# digital.net
KiCad netlist of a schematic drawn in EAGLE
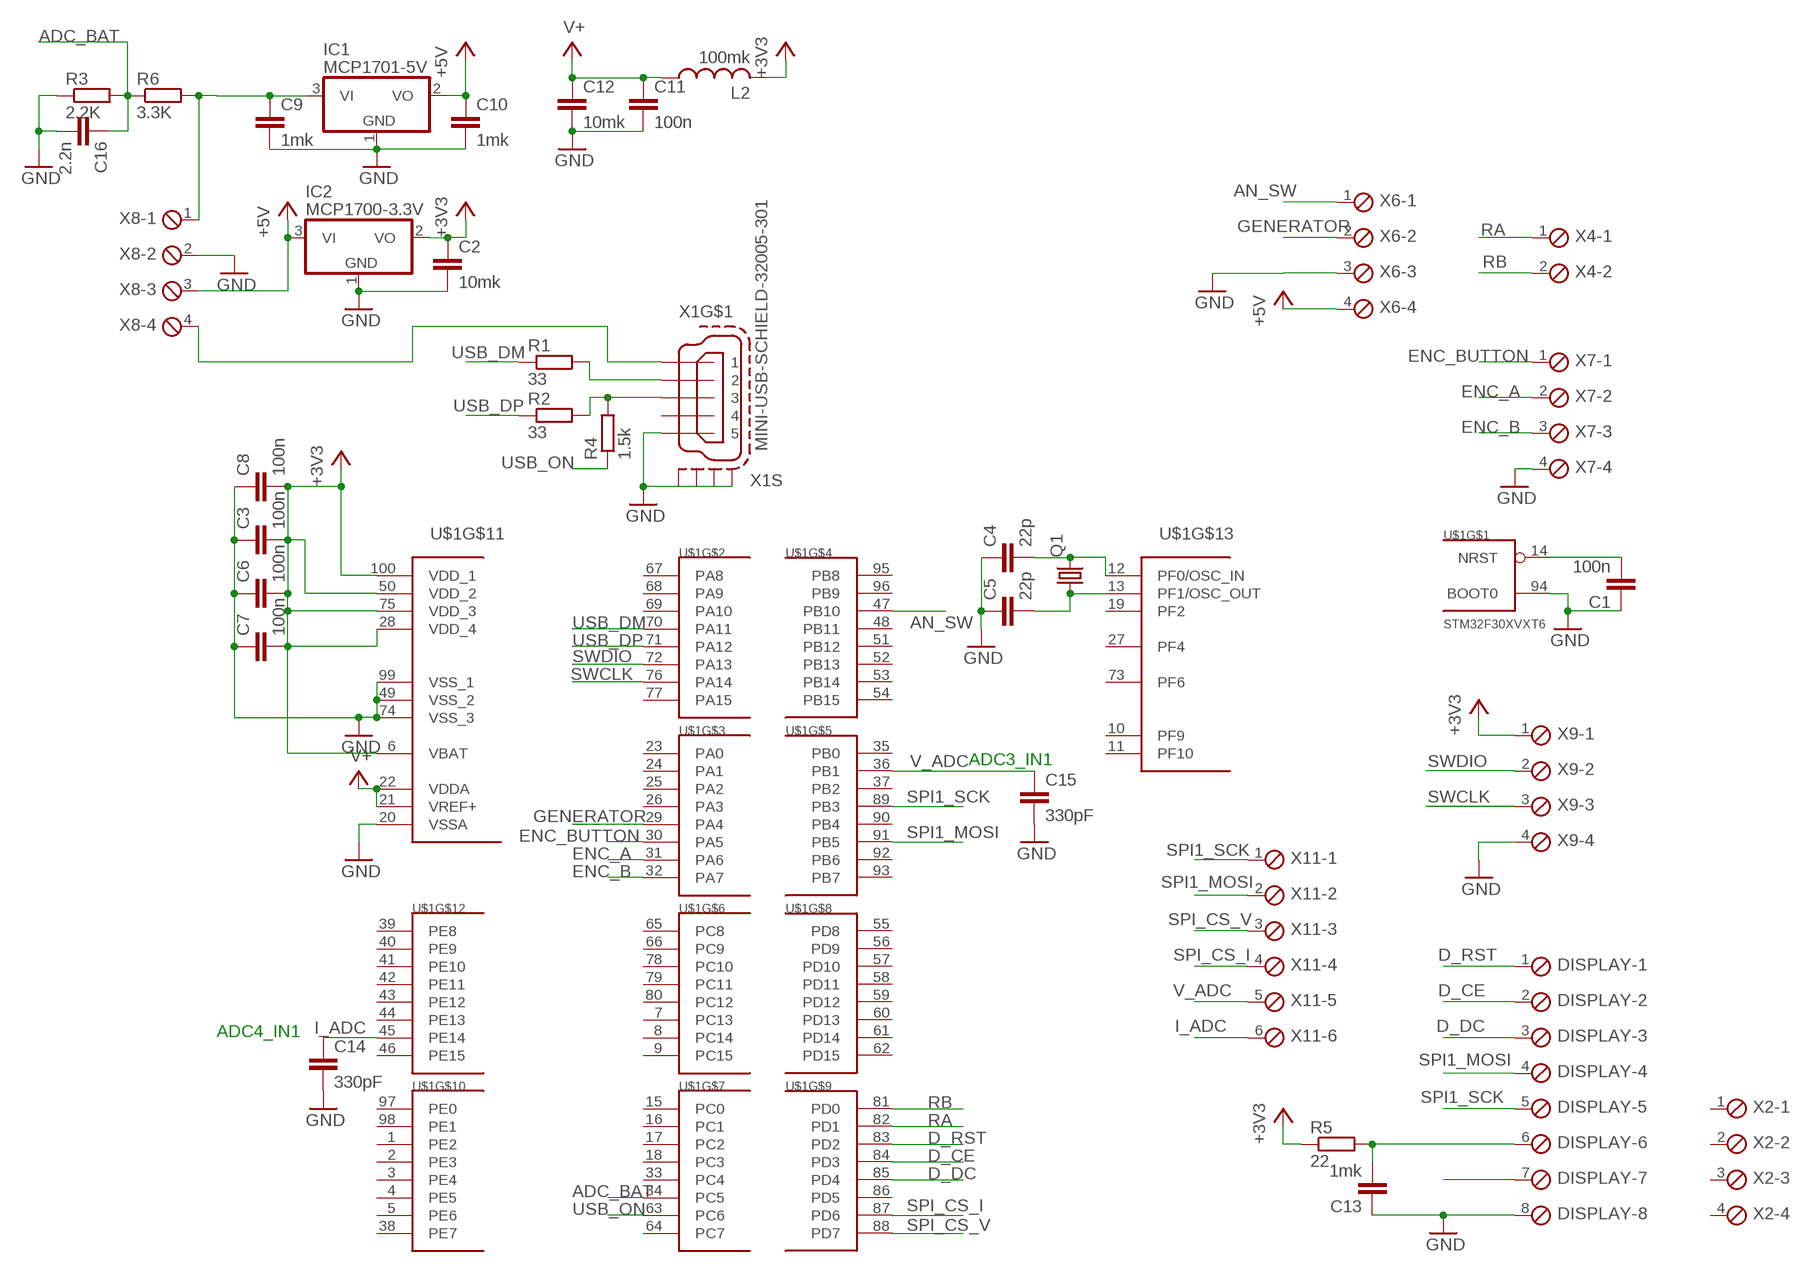
[diagram p0: schematic, sheet 1]

(export (version "E")
  (design (tool "Eeschema 10.0.6"))
  (components
    (comp (ref "C1")
      (value "100n")
      (footprint "eagle-import:C0603")
      (libsource (lib "eagle-import") (part "C-EUC0603"))
    )
    (comp (ref "C2")
      (value "10mk")
      (footprint "eagle-import:C0805")
      (libsource (lib "eagle-import") (part "C-EUC0805"))
    )
    (comp (ref "C3")
      (value "100n")
      (footprint "eagle-import:C0603")
      (libsource (lib "eagle-import") (part "C-EUC0603"))
    )
    (comp (ref "C4")
      (value "22p")
      (footprint "eagle-import:C0805")
      (libsource (lib "eagle-import") (part "C-EUC0805"))
    )
    (comp (ref "C5")
      (value "22p")
      (footprint "eagle-import:C0805")
      (libsource (lib "eagle-import") (part "C-EUC0805"))
    )
    (comp (ref "C6")
      (value "100n")
      (footprint "eagle-import:C0603")
      (libsource (lib "eagle-import") (part "C-EUC0603"))
    )
    (comp (ref "C7")
      (value "100n")
      (footprint "eagle-import:C0603")
      (libsource (lib "eagle-import") (part "C-EUC0603"))
    )
    (comp (ref "C8")
      (value "100n")
      (footprint "eagle-import:C0603")
      (libsource (lib "eagle-import") (part "C-EUC0603"))
    )
    (comp (ref "C9")
      (value "1mk")
      (footprint "eagle-import:C0603")
      (libsource (lib "eagle-import") (part "C-EUC0603"))
    )
    (comp (ref "C10")
      (value "1mk")
      (footprint "eagle-import:C0603")
      (libsource (lib "eagle-import") (part "C-EUC0603"))
    )
    (comp (ref "C11")
      (value "100n")
      (footprint "eagle-import:C0603")
      (libsource (lib "eagle-import") (part "C-EUC0603"))
    )
    (comp (ref "C12")
      (value "10mk")
      (footprint "eagle-import:C0805")
      (libsource (lib "eagle-import") (part "C-EUC0805"))
    )
    (comp (ref "C13")
      (value "1mk")
      (footprint "eagle-import:C0603")
      (libsource (lib "eagle-import") (part "C-EUC0603"))
    )
    (comp (ref "C14")
      (value "330pF")
      (footprint "eagle-import:C0805")
      (libsource (lib "eagle-import") (part "C-EUC0805"))
    )
    (comp (ref "C15")
      (value "330pF")
      (footprint "eagle-import:C0805")
      (libsource (lib "eagle-import") (part "C-EUC0805"))
    )
    (comp (ref "C16")
      (value "2.2n")
      (footprint "eagle-import:C0805")
      (libsource (lib "eagle-import") (part "C-EUC0805"))
    )
    (comp (ref "DISPLAY")
      (value "MPT8")
      (footprint "eagle-import:8POL254")
      (libsource (lib "eagle-import") (part "MPT8"))
    )
    (comp (ref "IC1")
      (value "MCP1701-5V")
      (footprint "eagle-import:SOT23")
      (libsource (lib "eagle-import") (part "MCP1703CB"))
    )
    (comp (ref "IC2")
      (value "MCP1700-3.3V")
      (footprint "eagle-import:SOT23")
      (libsource (lib "eagle-import") (part "MCP1703CB"))
    )
    (comp (ref "L2")
      (value "100mk")
      (footprint "eagle-import:0204_7")
      (libsource (lib "eagle-import") (part "L-US0204/7"))
    )
    (comp (ref "Q1")
      (value "CRYSTALHC49UP")
      (footprint "eagle-import:HC49UP")
      (libsource (lib "eagle-import") (part "CRYSTALHC49UP"))
    )
    (comp (ref "R1")
      (value "33")
      (footprint "eagle-import:R0603")
      (libsource (lib "eagle-import") (part "R-EU_R0603"))
    )
    (comp (ref "R2")
      (value "33")
      (footprint "eagle-import:R0603")
      (libsource (lib "eagle-import") (part "R-EU_R0603"))
    )
    (comp (ref "R3")
      (value "2.2K")
      (footprint "eagle-import:R0603")
      (libsource (lib "eagle-import") (part "R-EU_R0603"))
    )
    (comp (ref "R4")
      (value "1.5k")
      (footprint "eagle-import:R0603")
      (libsource (lib "eagle-import") (part "R-EU_R0603"))
    )
    (comp (ref "R5")
      (value "22")
      (footprint "eagle-import:R0603")
      (libsource (lib "eagle-import") (part "R-EU_R0603"))
    )
    (comp (ref "R6")
      (value "3.3K")
      (footprint "eagle-import:R0603")
      (libsource (lib "eagle-import") (part "R-EU_R0603"))
    )
    (comp (ref "U$1")
      (value "STM32F30XVXT6")
      (footprint "eagle-import:TQFP100")
      (libsource (lib "eagle-import") (part "STM32F30XVXT6"))
    )
    (comp (ref "X1")
      (value "MINI-USB-SCHIELD-32005-301")
      (footprint "eagle-import:32005-301")
      (libsource (lib "eagle-import") (part "MINI-USB-SCHIELD-32005-301"))
    )
    (comp (ref "X2")
      (value "MPT4")
      (footprint "eagle-import:4POL254")
      (libsource (lib "eagle-import") (part "MPT4"))
    )
    (comp (ref "X4")
      (value "MPT2")
      (footprint "eagle-import:2POL254")
      (libsource (lib "eagle-import") (part "MPT2"))
    )
    (comp (ref "X6")
      (value "MPT4")
      (footprint "eagle-import:4POL254")
      (libsource (lib "eagle-import") (part "MPT4"))
    )
    (comp (ref "X7")
      (value "MPT4")
      (footprint "eagle-import:4POL254")
      (libsource (lib "eagle-import") (part "MPT4"))
    )
    (comp (ref "X8")
      (value "MPT4")
      (footprint "eagle-import:4POL254")
      (libsource (lib "eagle-import") (part "MPT4"))
    )
    (comp (ref "X9")
      (value "MPT4")
      (footprint "eagle-import:4POL254")
      (libsource (lib "eagle-import") (part "MPT4"))
    )
    (comp (ref "X11")
      (value "MPT6")
      (footprint "eagle-import:6POL254")
      (libsource (lib "eagle-import") (part "MPT6"))
    )
  )
  (nets
    (net (code "1") (name "+3V3") (class "Default")
      (node (ref "C2") (pin "1") (pinfunction "1_1") (pintype "passive"))
      (node (ref "C3") (pin "2") (pinfunction "2_2") (pintype "passive"))
      (node (ref "C6") (pin "2") (pinfunction "2_2") (pintype "passive"))
      (node (ref "C7") (pin "2") (pinfunction "2_2") (pintype "passive"))
      (node (ref "C8") (pin "2") (pinfunction "2_2") (pintype "passive"))
      (node (ref "IC2") (pin "2") (pinfunction "VO_2") (pintype "passive"))
      (node (ref "L2") (pin "2") (pinfunction "2_2") (pintype "passive"))
      (node (ref "R5") (pin "1") (pinfunction "1_1") (pintype "passive"))
      (node (ref "U$1") (pin "100") (pinfunction "VDD_1_100") (pintype "bidirectional"))
      (node (ref "U$1") (pin "28") (pinfunction "VDD_4_28") (pintype "bidirectional"))
      (node (ref "U$1") (pin "50") (pinfunction "VDD_2_50") (pintype "bidirectional"))
      (node (ref "U$1") (pin "6") (pinfunction "VBAT_6") (pintype "bidirectional"))
      (node (ref "U$1") (pin "75") (pinfunction "VDD_3_75") (pintype "bidirectional"))
      (node (ref "X9") (pin "1") (pinfunction "1_1") (pintype "passive"))
    )
    (net (code "2") (name "+5V") (class "Default")
      (node (ref "C10") (pin "1") (pinfunction "1_1") (pintype "passive"))
      (node (ref "IC1") (pin "2") (pinfunction "VO_2") (pintype "passive"))
      (node (ref "IC2") (pin "3") (pinfunction "VI_3") (pintype "input"))
      (node (ref "X6") (pin "4") (pinfunction "1_4") (pintype "passive"))
      (node (ref "X8") (pin "3") (pinfunction "1_3") (pintype "passive"))
    )
    (net (code "3") (name "/ADC_BAT") (class "Default")
      (node (ref "C16") (pin "1") (pinfunction "1_1") (pintype "passive"))
      (node (ref "R3") (pin "2") (pinfunction "2_2") (pintype "passive"))
      (node (ref "R6") (pin "1") (pinfunction "1_1") (pintype "passive"))
      (node (ref "U$1") (pin "34") (pinfunction "PC5_34") (pintype "bidirectional"))
    )
    (net (code "4") (name "/AN_SW") (class "Default")
      (node (ref "U$1") (pin "47") (pinfunction "PB10_47") (pintype "bidirectional"))
      (node (ref "X6") (pin "1") (pinfunction "1_1") (pintype "passive"))
    )
    (net (code "5") (name "/D_CE") (class "Default")
      (node (ref "DISPLAY") (pin "2") (pinfunction "1_2") (pintype "passive"))
      (node (ref "U$1") (pin "84") (pinfunction "PD3_84") (pintype "bidirectional"))
    )
    (net (code "6") (name "/D_DC") (class "Default")
      (node (ref "DISPLAY") (pin "3") (pinfunction "1_3") (pintype "passive"))
      (node (ref "U$1") (pin "85") (pinfunction "PD4_85") (pintype "bidirectional"))
    )
    (net (code "7") (name "/D_RST") (class "Default")
      (node (ref "DISPLAY") (pin "1") (pinfunction "1_1") (pintype "passive"))
      (node (ref "U$1") (pin "83") (pinfunction "PD2_83") (pintype "bidirectional"))
    )
    (net (code "8") (name "/ENC_A") (class "Default")
      (node (ref "U$1") (pin "31") (pinfunction "PA6_31") (pintype "bidirectional"))
      (node (ref "X7") (pin "2") (pinfunction "1_2") (pintype "passive"))
    )
    (net (code "9") (name "/ENC_B") (class "Default")
      (node (ref "U$1") (pin "32") (pinfunction "PA7_32") (pintype "bidirectional"))
      (node (ref "X7") (pin "3") (pinfunction "1_3") (pintype "passive"))
    )
    (net (code "10") (name "/ENC_BUTTON") (class "Default")
      (node (ref "U$1") (pin "30") (pinfunction "PA5_30") (pintype "bidirectional"))
      (node (ref "X7") (pin "1") (pinfunction "1_1") (pintype "passive"))
    )
    (net (code "11") (name "/GENERATOR") (class "Default")
      (node (ref "U$1") (pin "29") (pinfunction "PA4_29") (pintype "bidirectional"))
      (node (ref "X6") (pin "2") (pinfunction "1_2") (pintype "passive"))
    )
    (net (code "12") (name "/I_ADC") (class "Default")
      (node (ref "C14") (pin "1") (pinfunction "1_1") (pintype "passive"))
      (node (ref "U$1") (pin "45") (pinfunction "PE14_45") (pintype "bidirectional"))
      (node (ref "X11") (pin "6") (pinfunction "1_6") (pintype "passive"))
    )
    (net (code "13") (name "/RA") (class "Default")
      (node (ref "U$1") (pin "82") (pinfunction "PD1_82") (pintype "bidirectional"))
      (node (ref "X4") (pin "1") (pinfunction "1_1") (pintype "passive"))
    )
    (net (code "14") (name "/RB") (class "Default")
      (node (ref "U$1") (pin "81") (pinfunction "PD0_81") (pintype "bidirectional"))
      (node (ref "X4") (pin "2") (pinfunction "1_2") (pintype "passive"))
    )
    (net (code "15") (name "/SPI1_MOSI") (class "Default")
      (node (ref "DISPLAY") (pin "4") (pinfunction "1_4") (pintype "passive"))
      (node (ref "U$1") (pin "91") (pinfunction "PB5_91") (pintype "bidirectional"))
      (node (ref "X11") (pin "2") (pinfunction "1_2") (pintype "passive"))
    )
    (net (code "16") (name "/SPI1_SCK") (class "Default")
      (node (ref "DISPLAY") (pin "5") (pinfunction "1_5") (pintype "passive"))
      (node (ref "U$1") (pin "89") (pinfunction "PB3_89") (pintype "bidirectional"))
      (node (ref "X11") (pin "1") (pinfunction "1_1") (pintype "passive"))
    )
    (net (code "17") (name "/SPI_CS_I") (class "Default")
      (node (ref "U$1") (pin "87") (pinfunction "PD6_87") (pintype "bidirectional"))
      (node (ref "X11") (pin "4") (pinfunction "1_4") (pintype "passive"))
    )
    (net (code "18") (name "/SPI_CS_V") (class "Default")
      (node (ref "U$1") (pin "88") (pinfunction "PD7_88") (pintype "bidirectional"))
      (node (ref "X11") (pin "3") (pinfunction "1_3") (pintype "passive"))
    )
    (net (code "19") (name "/SWCLK") (class "Default")
      (node (ref "U$1") (pin "76") (pinfunction "PA14_76") (pintype "bidirectional"))
      (node (ref "X9") (pin "3") (pinfunction "1_3") (pintype "passive"))
    )
    (net (code "20") (name "/SWDIO") (class "Default")
      (node (ref "U$1") (pin "72") (pinfunction "PA13_72") (pintype "bidirectional"))
      (node (ref "X9") (pin "2") (pinfunction "1_2") (pintype "passive"))
    )
    (net (code "21") (name "/USB_DM") (class "Default")
      (node (ref "R1") (pin "1") (pinfunction "1_1") (pintype "passive"))
      (node (ref "U$1") (pin "70") (pinfunction "PA11_70") (pintype "bidirectional"))
    )
    (net (code "22") (name "/USB_DP") (class "Default")
      (node (ref "R2") (pin "1") (pinfunction "1_1") (pintype "passive"))
      (node (ref "U$1") (pin "71") (pinfunction "PA12_71") (pintype "bidirectional"))
    )
    (net (code "23") (name "/USB_ON") (class "Default")
      (node (ref "R4") (pin "1") (pinfunction "1_1") (pintype "passive"))
      (node (ref "U$1") (pin "63") (pinfunction "PC6_63") (pintype "bidirectional"))
    )
    (net (code "24") (name "/V_ADC") (class "Default")
      (node (ref "C15") (pin "1") (pinfunction "1_1") (pintype "passive"))
      (node (ref "U$1") (pin "36") (pinfunction "PB1_36") (pintype "bidirectional"))
      (node (ref "X11") (pin "5") (pinfunction "1_5") (pintype "passive"))
    )
    (net (code "25") (name "GND") (class "Default")
      (node (ref "C1") (pin "1") (pinfunction "1_1") (pintype "passive"))
      (node (ref "C10") (pin "2") (pinfunction "2_2") (pintype "passive"))
      (node (ref "C11") (pin "2") (pinfunction "2_2") (pintype "passive"))
      (node (ref "C12") (pin "2") (pinfunction "2_2") (pintype "passive"))
      (node (ref "C13") (pin "1") (pinfunction "1_1") (pintype "passive"))
      (node (ref "C14") (pin "2") (pinfunction "2_2") (pintype "passive"))
      (node (ref "C15") (pin "2") (pinfunction "2_2") (pintype "passive"))
      (node (ref "C16") (pin "2") (pinfunction "2_2") (pintype "passive"))
      (node (ref "C2") (pin "2") (pinfunction "2_2") (pintype "passive"))
      (node (ref "C3") (pin "1") (pinfunction "1_1") (pintype "passive"))
      (node (ref "C4") (pin "1") (pinfunction "1_1") (pintype "passive"))
      (node (ref "C5") (pin "1") (pinfunction "1_1") (pintype "passive"))
      (node (ref "C6") (pin "1") (pinfunction "1_1") (pintype "passive"))
      (node (ref "C7") (pin "1") (pinfunction "1_1") (pintype "passive"))
      (node (ref "C8") (pin "1") (pinfunction "1_1") (pintype "passive"))
      (node (ref "C9") (pin "2") (pinfunction "2_2") (pintype "passive"))
      (node (ref "DISPLAY") (pin "8") (pinfunction "1_8") (pintype "passive"))
      (node (ref "IC1") (pin "1") (pinfunction "GND_1") (pintype "passive"))
      (node (ref "IC2") (pin "1") (pinfunction "GND_1") (pintype "passive"))
      (node (ref "R3") (pin "1") (pinfunction "1_1") (pintype "passive"))
      (node (ref "U$1") (pin "20") (pinfunction "VSSA_20") (pintype "bidirectional"))
      (node (ref "U$1") (pin "49") (pinfunction "VSS_2_49") (pintype "bidirectional"))
      (node (ref "U$1") (pin "74") (pinfunction "VSS_3_74") (pintype "bidirectional"))
      (node (ref "U$1") (pin "94") (pinfunction "BOOT0_94") (pintype "input"))
      (node (ref "U$1") (pin "99") (pinfunction "VSS_1_99") (pintype "bidirectional"))
      (node (ref "X1") (pin "5") (pinfunction "5_5") (pintype "passive"))
      (node (ref "X1") (pin "M1") (pinfunction "S1_M1") (pintype "passive"))
      (node (ref "X1") (pin "M2") (pinfunction "S2_M2") (pintype "passive"))
      (node (ref "X1") (pin "M3") (pinfunction "S3_M3") (pintype "passive"))
      (node (ref "X1") (pin "M4") (pinfunction "S4_M4") (pintype "passive"))
      (node (ref "X6") (pin "3") (pinfunction "1_3") (pintype "passive"))
      (node (ref "X7") (pin "4") (pinfunction "1_4") (pintype "passive"))
      (node (ref "X8") (pin "2") (pinfunction "1_2") (pintype "passive"))
      (node (ref "X9") (pin "4") (pinfunction "1_4") (pintype "passive"))
    )
    (net (code "26") (name "Net-(DISPLAYF-1)") (class "Default")
      (node (ref "C13") (pin "2") (pinfunction "2_2") (pintype "passive"))
      (node (ref "DISPLAY") (pin "6") (pinfunction "1_6") (pintype "passive"))
      (node (ref "R5") (pin "2") (pinfunction "2_2") (pintype "passive"))
    )
    (net (code "27") (name "Net-(IC1-VI)") (class "Default")
      (node (ref "C9") (pin "1") (pinfunction "1_1") (pintype "passive"))
      (node (ref "IC1") (pin "3") (pinfunction "VI_3") (pintype "input"))
      (node (ref "R6") (pin "2") (pinfunction "2_2") (pintype "passive"))
      (node (ref "X8") (pin "1") (pinfunction "1_1") (pintype "passive"))
    )
    (net (code "28") (name "Net-(R1-Pad2)") (class "Default")
      (node (ref "R1") (pin "2") (pinfunction "2_2") (pintype "passive"))
      (node (ref "X1") (pin "2") (pinfunction "2_2") (pintype "passive"))
    )
    (net (code "29") (name "Net-(R2-Pad2)") (class "Default")
      (node (ref "R2") (pin "2") (pinfunction "2_2") (pintype "passive"))
      (node (ref "R4") (pin "2") (pinfunction "2_2") (pintype "passive"))
      (node (ref "X1") (pin "3") (pinfunction "3_3") (pintype "passive"))
    )
    (net (code "30") (name "Net-(U$1A-NRST)") (class "Default")
      (node (ref "C1") (pin "2") (pinfunction "2_2") (pintype "passive"))
      (node (ref "U$1") (pin "14") (pinfunction "NRST_14") (pintype "input"))
    )
    (net (code "31") (name "Net-(U$1E-PF0{slash}OSC_IN)") (class "Default")
      (node (ref "C4") (pin "2") (pinfunction "2_2") (pintype "passive"))
      (node (ref "Q1") (pin "2") (pinfunction "2_2") (pintype "passive"))
      (node (ref "U$1") (pin "12") (pinfunction "PF0/OSC_IN_12") (pintype "bidirectional"))
    )
    (net (code "32") (name "Net-(U$1E-PF1{slash}OSC_OUT)") (class "Default")
      (node (ref "C5") (pin "2") (pinfunction "2_2") (pintype "passive"))
      (node (ref "Q1") (pin "1") (pinfunction "1_1") (pintype "passive"))
      (node (ref "U$1") (pin "13") (pinfunction "PF1/OSC_OUT_13") (pintype "bidirectional"))
    )
    (net (code "33") (name "Net-(X8D-1)") (class "Default")
      (node (ref "X1") (pin "1") (pinfunction "1_1") (pintype "passive"))
      (node (ref "X8") (pin "4") (pinfunction "1_4") (pintype "passive"))
    )
    (net (code "34") (name "V+") (class "Default")
      (node (ref "C11") (pin "1") (pinfunction "1_1") (pintype "passive"))
      (node (ref "C12") (pin "1") (pinfunction "1_1") (pintype "passive"))
      (node (ref "L2") (pin "1") (pinfunction "1_1") (pintype "passive"))
      (node (ref "U$1") (pin "21") (pinfunction "VREF+_21") (pintype "bidirectional"))
      (node (ref "U$1") (pin "22") (pinfunction "VDDA_22") (pintype "bidirectional"))
    )
    (net (code "35") (name "unconnected-(DISPLAYG-1-Pad7)") (class "Default")
      (node (ref "DISPLAY") (pin "7") (pinfunction "1_7") (pintype "passive"))
    )
    (net (code "36") (name "unconnected-(U$1B-PE0-Pad97)") (class "Default")
      (node (ref "U$1") (pin "97") (pinfunction "PE0_97") (pintype "bidirectional"))
    )
    (net (code "37") (name "unconnected-(U$1B-PE1-Pad98)") (class "Default")
      (node (ref "U$1") (pin "98") (pinfunction "PE1_98") (pintype "bidirectional"))
    )
    (net (code "38") (name "unconnected-(U$1B-PE2-Pad1)") (class "Default")
      (node (ref "U$1") (pin "1") (pinfunction "PE2_1") (pintype "bidirectional"))
    )
    (net (code "39") (name "unconnected-(U$1B-PE3-Pad2)") (class "Default")
      (node (ref "U$1") (pin "2") (pinfunction "PE3_2") (pintype "bidirectional"))
    )
    (net (code "40") (name "unconnected-(U$1B-PE4-Pad3)") (class "Default")
      (node (ref "U$1") (pin "3") (pinfunction "PE4_3") (pintype "bidirectional"))
    )
    (net (code "41") (name "unconnected-(U$1B-PE5-Pad4)") (class "Default")
      (node (ref "U$1") (pin "4") (pinfunction "PE5_4") (pintype "bidirectional"))
    )
    (net (code "42") (name "unconnected-(U$1B-PE6-Pad5)") (class "Default")
      (node (ref "U$1") (pin "5") (pinfunction "PE6_5") (pintype "bidirectional"))
    )
    (net (code "43") (name "unconnected-(U$1B-PE7-Pad38)") (class "Default")
      (node (ref "U$1") (pin "38") (pinfunction "PE7_38") (pintype "bidirectional"))
    )
    (net (code "44") (name "unconnected-(U$1D-PE8-Pad39)") (class "Default")
      (node (ref "U$1") (pin "39") (pinfunction "PE8_39") (pintype "bidirectional"))
    )
    (net (code "45") (name "unconnected-(U$1D-PE9-Pad40)") (class "Default")
      (node (ref "U$1") (pin "40") (pinfunction "PE9_40") (pintype "bidirectional"))
    )
    (net (code "46") (name "unconnected-(U$1D-PE10-Pad41)") (class "Default")
      (node (ref "U$1") (pin "41") (pinfunction "PE10_41") (pintype "bidirectional"))
    )
    (net (code "47") (name "unconnected-(U$1D-PE11-Pad42)") (class "Default")
      (node (ref "U$1") (pin "42") (pinfunction "PE11_42") (pintype "bidirectional"))
    )
    (net (code "48") (name "unconnected-(U$1D-PE12-Pad43)") (class "Default")
      (node (ref "U$1") (pin "43") (pinfunction "PE12_43") (pintype "bidirectional"))
    )
    (net (code "49") (name "unconnected-(U$1D-PE13-Pad44)") (class "Default")
      (node (ref "U$1") (pin "44") (pinfunction "PE13_44") (pintype "bidirectional"))
    )
    (net (code "50") (name "unconnected-(U$1D-PE15-Pad46)") (class "Default")
      (node (ref "U$1") (pin "46") (pinfunction "PE15_46") (pintype "bidirectional"))
    )
    (net (code "51") (name "unconnected-(U$1E-PF2-Pad19)") (class "Default")
      (node (ref "U$1") (pin "19") (pinfunction "PF2_19") (pintype "bidirectional"))
    )
    (net (code "52") (name "unconnected-(U$1E-PF4-Pad27)") (class "Default")
      (node (ref "U$1") (pin "27") (pinfunction "PF4_27") (pintype "bidirectional"))
    )
    (net (code "53") (name "unconnected-(U$1E-PF6-Pad73)") (class "Default")
      (node (ref "U$1") (pin "73") (pinfunction "PF6_73") (pintype "bidirectional"))
    )
    (net (code "54") (name "unconnected-(U$1E-PF9-Pad10)") (class "Default")
      (node (ref "U$1") (pin "10") (pinfunction "PF9_10") (pintype "bidirectional"))
    )
    (net (code "55") (name "unconnected-(U$1E-PF10-Pad11)") (class "Default")
      (node (ref "U$1") (pin "11") (pinfunction "PF10_11") (pintype "bidirectional"))
    )
    (net (code "56") (name "unconnected-(U$1F-PA8-Pad67)") (class "Default")
      (node (ref "U$1") (pin "67") (pinfunction "PA8_67") (pintype "bidirectional"))
    )
    (net (code "57") (name "unconnected-(U$1F-PA9-Pad68)") (class "Default")
      (node (ref "U$1") (pin "68") (pinfunction "PA9_68") (pintype "bidirectional"))
    )
    (net (code "58") (name "unconnected-(U$1F-PA10-Pad69)") (class "Default")
      (node (ref "U$1") (pin "69") (pinfunction "PA10_69") (pintype "bidirectional"))
    )
    (net (code "59") (name "unconnected-(U$1F-PA15-Pad77)") (class "Default")
      (node (ref "U$1") (pin "77") (pinfunction "PA15_77") (pintype "bidirectional"))
    )
    (net (code "60") (name "unconnected-(U$1G-PA0-Pad23)") (class "Default")
      (node (ref "U$1") (pin "23") (pinfunction "PA0_23") (pintype "bidirectional"))
    )
    (net (code "61") (name "unconnected-(U$1G-PA1-Pad24)") (class "Default")
      (node (ref "U$1") (pin "24") (pinfunction "PA1_24") (pintype "bidirectional"))
    )
    (net (code "62") (name "unconnected-(U$1G-PA2-Pad25)") (class "Default")
      (node (ref "U$1") (pin "25") (pinfunction "PA2_25") (pintype "bidirectional"))
    )
    (net (code "63") (name "unconnected-(U$1G-PA3-Pad26)") (class "Default")
      (node (ref "U$1") (pin "26") (pinfunction "PA3_26") (pintype "bidirectional"))
    )
    (net (code "64") (name "unconnected-(U$1H-PB8-Pad95)") (class "Default")
      (node (ref "U$1") (pin "95") (pinfunction "PB8_95") (pintype "bidirectional"))
    )
    (net (code "65") (name "unconnected-(U$1H-PB9-Pad96)") (class "Default")
      (node (ref "U$1") (pin "96") (pinfunction "PB9_96") (pintype "bidirectional"))
    )
    (net (code "66") (name "unconnected-(U$1H-PB11-Pad48)") (class "Default")
      (node (ref "U$1") (pin "48") (pinfunction "PB11_48") (pintype "bidirectional"))
    )
    (net (code "67") (name "unconnected-(U$1H-PB12-Pad51)") (class "Default")
      (node (ref "U$1") (pin "51") (pinfunction "PB12_51") (pintype "bidirectional"))
    )
    (net (code "68") (name "unconnected-(U$1H-PB13-Pad52)") (class "Default")
      (node (ref "U$1") (pin "52") (pinfunction "PB13_52") (pintype "bidirectional"))
    )
    (net (code "69") (name "unconnected-(U$1H-PB14-Pad53)") (class "Default")
      (node (ref "U$1") (pin "53") (pinfunction "PB14_53") (pintype "bidirectional"))
    )
    (net (code "70") (name "unconnected-(U$1H-PB15-Pad54)") (class "Default")
      (node (ref "U$1") (pin "54") (pinfunction "PB15_54") (pintype "bidirectional"))
    )
    (net (code "71") (name "unconnected-(U$1I-PB0-Pad35)") (class "Default")
      (node (ref "U$1") (pin "35") (pinfunction "PB0_35") (pintype "bidirectional"))
    )
    (net (code "72") (name "unconnected-(U$1I-PB2-Pad37)") (class "Default")
      (node (ref "U$1") (pin "37") (pinfunction "PB2_37") (pintype "bidirectional"))
    )
    (net (code "73") (name "unconnected-(U$1I-PB4-Pad90)") (class "Default")
      (node (ref "U$1") (pin "90") (pinfunction "PB4_90") (pintype "bidirectional"))
    )
    (net (code "74") (name "unconnected-(U$1I-PB6-Pad92)") (class "Default")
      (node (ref "U$1") (pin "92") (pinfunction "PB6_92") (pintype "bidirectional"))
    )
    (net (code "75") (name "unconnected-(U$1I-PB7-Pad93)") (class "Default")
      (node (ref "U$1") (pin "93") (pinfunction "PB7_93") (pintype "bidirectional"))
    )
    (net (code "76") (name "unconnected-(U$1J-PC8-Pad65)") (class "Default")
      (node (ref "U$1") (pin "65") (pinfunction "PC8_65") (pintype "bidirectional"))
    )
    (net (code "77") (name "unconnected-(U$1J-PC9-Pad66)") (class "Default")
      (node (ref "U$1") (pin "66") (pinfunction "PC9_66") (pintype "bidirectional"))
    )
    (net (code "78") (name "unconnected-(U$1J-PC10-Pad78)") (class "Default")
      (node (ref "U$1") (pin "78") (pinfunction "PC10_78") (pintype "bidirectional"))
    )
    (net (code "79") (name "unconnected-(U$1J-PC11-Pad79)") (class "Default")
      (node (ref "U$1") (pin "79") (pinfunction "PC11_79") (pintype "bidirectional"))
    )
    (net (code "80") (name "unconnected-(U$1J-PC12-Pad80)") (class "Default")
      (node (ref "U$1") (pin "80") (pinfunction "PC12_80") (pintype "bidirectional"))
    )
    (net (code "81") (name "unconnected-(U$1J-PC13-Pad7)") (class "Default")
      (node (ref "U$1") (pin "7") (pinfunction "PC13_7") (pintype "bidirectional"))
    )
    (net (code "82") (name "unconnected-(U$1J-PC14-Pad8)") (class "Default")
      (node (ref "U$1") (pin "8") (pinfunction "PC14_8") (pintype "bidirectional"))
    )
    (net (code "83") (name "unconnected-(U$1J-PC15-Pad9)") (class "Default")
      (node (ref "U$1") (pin "9") (pinfunction "PC15_9") (pintype "bidirectional"))
    )
    (net (code "84") (name "unconnected-(U$1K-PC0-Pad15)") (class "Default")
      (node (ref "U$1") (pin "15") (pinfunction "PC0_15") (pintype "bidirectional"))
    )
    (net (code "85") (name "unconnected-(U$1K-PC1-Pad16)") (class "Default")
      (node (ref "U$1") (pin "16") (pinfunction "PC1_16") (pintype "bidirectional"))
    )
    (net (code "86") (name "unconnected-(U$1K-PC2-Pad17)") (class "Default")
      (node (ref "U$1") (pin "17") (pinfunction "PC2_17") (pintype "bidirectional"))
    )
    (net (code "87") (name "unconnected-(U$1K-PC3-Pad18)") (class "Default")
      (node (ref "U$1") (pin "18") (pinfunction "PC3_18") (pintype "bidirectional"))
    )
    (net (code "88") (name "unconnected-(U$1K-PC4-Pad33)") (class "Default")
      (node (ref "U$1") (pin "33") (pinfunction "PC4_33") (pintype "bidirectional"))
    )
    (net (code "89") (name "unconnected-(U$1K-PC7-Pad64)") (class "Default")
      (node (ref "U$1") (pin "64") (pinfunction "PC7_64") (pintype "bidirectional"))
    )
    (net (code "90") (name "unconnected-(U$1L-PD8-Pad55)") (class "Default")
      (node (ref "U$1") (pin "55") (pinfunction "PD8_55") (pintype "bidirectional"))
    )
    (net (code "91") (name "unconnected-(U$1L-PD9-Pad56)") (class "Default")
      (node (ref "U$1") (pin "56") (pinfunction "PD9_56") (pintype "bidirectional"))
    )
    (net (code "92") (name "unconnected-(U$1L-PD10-Pad57)") (class "Default")
      (node (ref "U$1") (pin "57") (pinfunction "PD10_57") (pintype "bidirectional"))
    )
    (net (code "93") (name "unconnected-(U$1L-PD11-Pad58)") (class "Default")
      (node (ref "U$1") (pin "58") (pinfunction "PD11_58") (pintype "bidirectional"))
    )
    (net (code "94") (name "unconnected-(U$1L-PD12-Pad59)") (class "Default")
      (node (ref "U$1") (pin "59") (pinfunction "PD12_59") (pintype "bidirectional"))
    )
    (net (code "95") (name "unconnected-(U$1L-PD13-Pad60)") (class "Default")
      (node (ref "U$1") (pin "60") (pinfunction "PD13_60") (pintype "bidirectional"))
    )
    (net (code "96") (name "unconnected-(U$1L-PD14-Pad61)") (class "Default")
      (node (ref "U$1") (pin "61") (pinfunction "PD14_61") (pintype "bidirectional"))
    )
    (net (code "97") (name "unconnected-(U$1L-PD15-Pad62)") (class "Default")
      (node (ref "U$1") (pin "62") (pinfunction "PD15_62") (pintype "bidirectional"))
    )
    (net (code "98") (name "unconnected-(U$1M-PD5-Pad86)") (class "Default")
      (node (ref "U$1") (pin "86") (pinfunction "PD5_86") (pintype "bidirectional"))
    )
    (net (code "99") (name "unconnected-(X1-Pad4)") (class "Default")
      (node (ref "X1") (pin "4") (pinfunction "4_4") (pintype "passive"))
    )
    (net (code "100") (name "unconnected-(X2-Pad1)") (class "Default")
      (node (ref "X2") (pin "1") (pinfunction "1_1") (pintype "passive"))
    )
    (net (code "101") (name "unconnected-(X2B-1-Pad2)") (class "Default")
      (node (ref "X2") (pin "2") (pinfunction "1_2") (pintype "passive"))
    )
    (net (code "102") (name "unconnected-(X2C-1-Pad3)") (class "Default")
      (node (ref "X2") (pin "3") (pinfunction "1_3") (pintype "passive"))
    )
    (net (code "103") (name "unconnected-(X2D-1-Pad4)") (class "Default")
      (node (ref "X2") (pin "4") (pinfunction "1_4") (pintype "passive"))
    )
  )
)
